# Display.net
KiCad netlist of a schematic drawn in Altium Designer
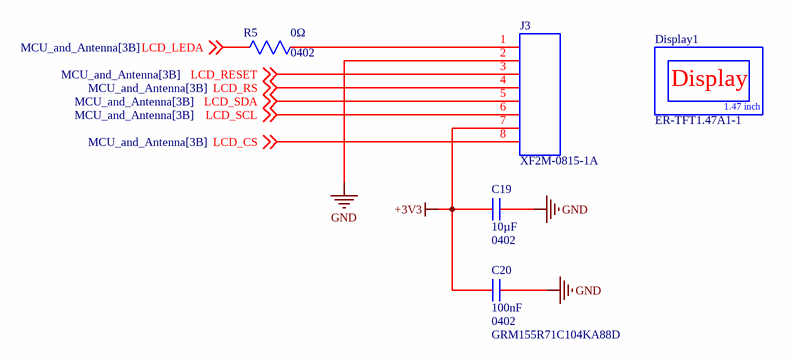
[diagram p0: Display.SchDoc]

(export (version "E")
  (design (tool "Eeschema 10.0.6"))
  (components
    (comp (ref "C19")
      (value "10µF")
      (footprint "CAPC1005X55N")
      (description "6.3V 10uF X5R ±20% 0402 Multilayer Ceramic Capacitors MLCC - SMD/SMT ROHS")
      (fields
        (field (name "MANUFACTURER") "Murata")
        (field (name "MANUFACTURER PART NUMBER") "GRM155R60J106ME15D")
        (field (name "CASE/PACKAGE") "0402")
      )
      (libsource (lib "Schlib") (part "GRM155R60J106ME15D"))
    )
    (comp (ref "C20")
      (value "GRM155R71C104KA88D")
      (footprint "CAPC1005X55N")
      (description "16V 100nF X7R ±10% 0402 Multilayer Ceramic Capacitors MLCC - SMD/SMT ROHS")
      (fields
        (field (name "MANUFACTURER") "Murata")
        (field (name "TOLERANCE") "10%")
        (field (name "CASE/PACKAGE") "0402")
        (field (name "ALTIUM_VALUE") "100nF")
      )
      (libsource (lib "Schlib") (part "GRM155R71C104KA88D"))
    )
    (comp (ref "Display1")
      (value "ER-TFT1.47A1-1")
      (description "1.47 inch IPS TFT LCD Display 172x320 ST7789 Connector Type FPC")
      (libsource (lib "Schlib") (part "ER-TFT1.47A1-1"))
    )
    (comp (ref "J3")
      (value "XF2M-0815-1A")
      (footprint "FPC connector 8pin, Pitch 0.5mm + Module_Display 1.14 inch")
      (description "Conn FFC/FPC Connector SKT 8 POS 0.5mm Solder RA SMD Reel")
      (fields
        (field (name "MANUFACTURER") "Omron Electronics Inc-EMC Div")
        (field (name "LCSC PART") "C3195305")
      )
      (libsource (lib "Schlib") (part "XF2M-0815-1A"))
    )
    (comp (ref "R5")
      (value "0Ω")
      (footprint "RC0402N_YAG-M")
      (description "GENERAL PURPOSE CHIP RESISTOR Metal Glaze/thick Film, 0.0625W, 0ohm, Surface Mount, 0402")
      (fields
        (field (name "MANUFACTURER") "Yageo Group")
        (field (name "MANUFACTURER PART NUMBER") "RC0402JR-070RL")
        (field (name "CASE/PACKAGE") "0402")
      )
      (libsource (lib "Schlib") (part "RC0402JR-070RL"))
    )
  )
  (nets
    (net (code "1") (name "+3V3") (class "Default")
      (node (ref "C19") (pin "2") (pinfunction "2_2") (pintype "passive"))
      (node (ref "C20") (pin "1") (pinfunction "1_1") (pintype "passive"))
      (node (ref "J3") (pin "7") (pinfunction "7_7") (pintype "passive"))
    )
    (net (code "2") (name "GND") (class "Default")
      (node (ref "C19") (pin "1") (pinfunction "1_1") (pintype "passive"))
      (node (ref "C20") (pin "2") (pinfunction "2_2") (pintype "passive"))
      (node (ref "J3") (pin "2") (pinfunction "2_2") (pintype "passive"))
    )
    (net (code "3") (name "LCD_CS") (class "Default")
      (node (ref "J3") (pin "8") (pinfunction "8_8") (pintype "passive"))
    )
    (net (code "4") (name "LCD_LEDA") (class "Default")
      (node (ref "R5") (pin "1") (pinfunction "1_1") (pintype "passive"))
    )
    (net (code "5") (name "LCD_RESET") (class "Default")
      (node (ref "J3") (pin "3") (pinfunction "3_3") (pintype "passive"))
    )
    (net (code "6") (name "LCD_RS") (class "Default")
      (node (ref "J3") (pin "4") (pinfunction "4_4") (pintype "passive"))
    )
    (net (code "7") (name "LCD_SCL") (class "Default")
      (node (ref "J3") (pin "6") (pinfunction "6_6") (pintype "passive"))
    )
    (net (code "8") (name "LCD_SDA") (class "Default")
      (node (ref "J3") (pin "5") (pinfunction "5_5") (pintype "passive"))
    )
    (net (code "9") (name "Net-(J3-Pad1)") (class "Default")
      (node (ref "J3") (pin "1") (pinfunction "1_1") (pintype "passive"))
      (node (ref "R5") (pin "2") (pinfunction "2_2") (pintype "passive"))
    )
  )
)
